# Rover_Motor_hat.net
KiCad netlist of a schematic drawn in Altium Designer
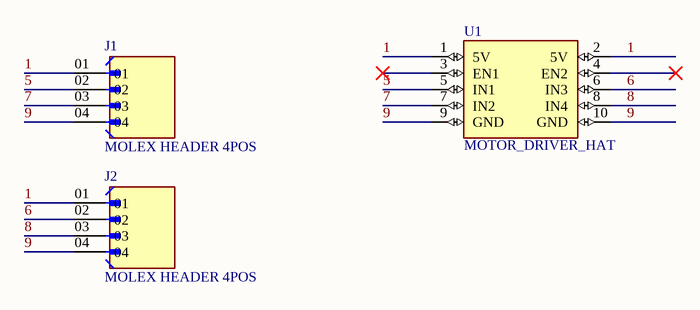
[diagram p0: Rover_Motor_hat.SchDoc]

(export (version "E")
  (design (tool "Eeschema 10.0.6"))
  (components
    (comp (ref "J1")
      (value "MOLEX HEADER 4POS")
      (footprint "MOLEX_35362-0450")
      (description "Connector Header Through Hole 4 position 0.079 (2.00mm)")
      (fields (field (name "MP") "35362-0450") (field (name "MF") "Molex"))
      (libsource (lib "35362-0450") (part "35362-0450"))
    )
    (comp (ref "J2")
      (value "MOLEX HEADER 4POS")
      (footprint "MOLEX_35362-0450")
      (description "Connector Header Through Hole 4 position 0.079 (2.00mm)")
      (fields (field (name "MP") "35362-0450") (field (name "MF") "Molex"))
      (libsource (lib "35362-0450") (part "35362-0450"))
    )
    (comp (ref "U1")
      (value "MOTOR_DRIVER_HAT")
      (footprint "MOTOR_DRIVER_HAT")
      (libsource (lib "Schlib2") (part "MOTOR_DRIVER_HAT"))
    )
  )
  (nets
    (net (code "1") (name "/1") (class "Default")
      (node (ref "J1") (pin "01") (pinfunction "01_01") (pintype "passive"))
      (node (ref "J2") (pin "01") (pinfunction "01_01") (pintype "passive"))
      (node (ref "U1") (pin "1") (pinfunction "5V_1") (pintype "bidirectional"))
      (node (ref "U1") (pin "2") (pinfunction "5V_2") (pintype "bidirectional"))
    )
    (net (code "2") (name "/5") (class "Default")
      (node (ref "J1") (pin "02") (pinfunction "02_02") (pintype "passive"))
      (node (ref "U1") (pin "5") (pinfunction "IN1_5") (pintype "bidirectional"))
    )
    (net (code "3") (name "/6") (class "Default")
      (node (ref "J2") (pin "02") (pinfunction "02_02") (pintype "passive"))
      (node (ref "U1") (pin "6") (pinfunction "IN3_6") (pintype "bidirectional"))
    )
    (net (code "4") (name "/7") (class "Default")
      (node (ref "J1") (pin "03") (pinfunction "03_03") (pintype "passive"))
      (node (ref "U1") (pin "7") (pinfunction "IN2_7") (pintype "bidirectional"))
    )
    (net (code "5") (name "/8") (class "Default")
      (node (ref "J2") (pin "03") (pinfunction "03_03") (pintype "passive"))
      (node (ref "U1") (pin "8") (pinfunction "IN4_8") (pintype "bidirectional"))
    )
    (net (code "6") (name "/9") (class "Default")
      (node (ref "J1") (pin "04") (pinfunction "04_04") (pintype "passive"))
      (node (ref "J2") (pin "04") (pinfunction "04_04") (pintype "passive"))
      (node (ref "U1") (pin "10") (pinfunction "GND_10") (pintype "bidirectional"))
      (node (ref "U1") (pin "9") (pinfunction "GND_9") (pintype "bidirectional"))
    )
    (net (code "7") (name "unconnected-(U1-EN1-Pad3)") (class "Default")
      (node (ref "U1") (pin "3") (pinfunction "EN1_3") (pintype "bidirectional+no_connect"))
    )
    (net (code "8") (name "unconnected-(U1-EN2-Pad4)") (class "Default")
      (node (ref "U1") (pin "4") (pinfunction "EN2_4") (pintype "bidirectional+no_connect"))
    )
  )
)
